# A-GSM.net
KiCad netlist of a schematic drawn in Altium Designer
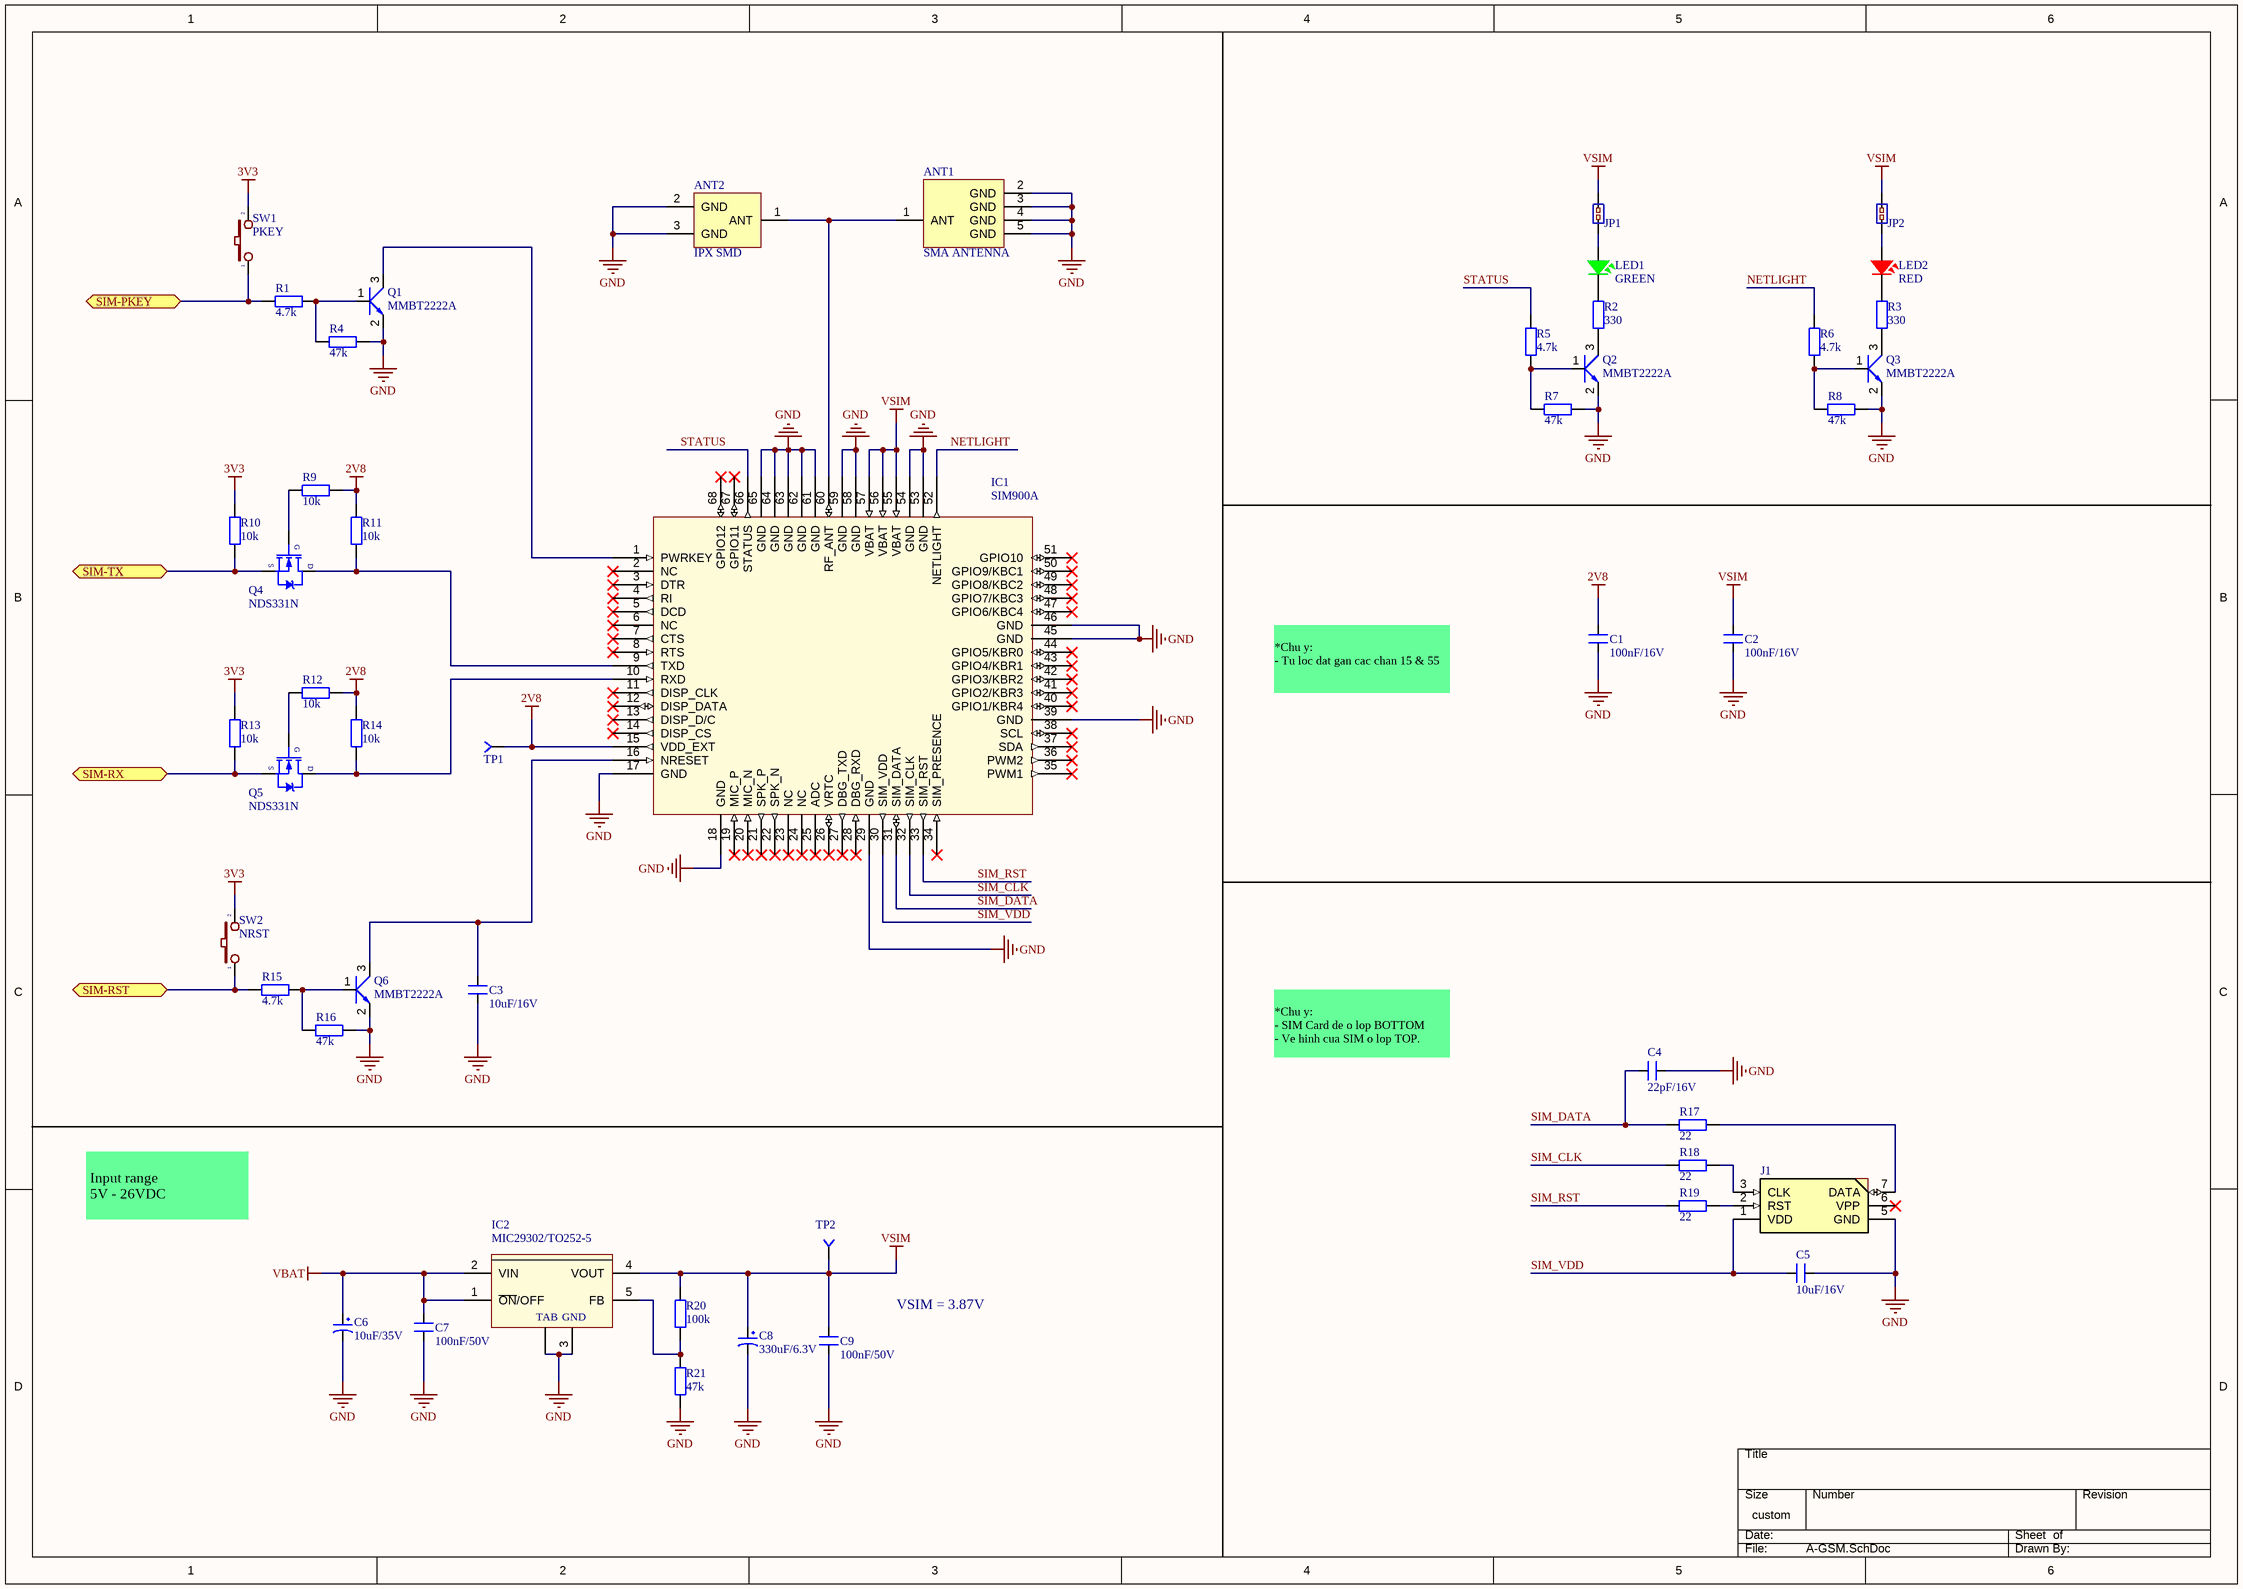
[diagram p0: A-GSM.SchDoc]

(export (version "E")
  (design (tool "Eeschema 10.0.6"))
  (components
    (comp (ref "ANT1")
      (value "SMA ANTENNA")
      (footprint "ANT-SMA-ST-F")
      (description "SMA Right-Angle PCB Female Antenna")
      (fields (field (name "Comment") "ANTEN-SMA"))
      (libsource (lib "Tran Tuan") (part "ANTEN-SMA"))
    )
    (comp (ref "ANT2")
      (value "IPX SMD")
      (footprint "ANT-IPX-SMD")
      (description "IPX, SMD, ANTENNA")
      (fields (field (name "Comment") "ANTEN-IPX"))
      (libsource (lib "Tran Tuan") (part "ANTEN-IPX"))
    )
    (comp (ref "C1")
      (value "100nF/16V")
      (footprint "C0805-2012")
      (description "CAP CER 0.1UF 16V X7R 0805")
      (fields
        (field (name "MANUFACTURER") "Kemet")
        (field (name "MANUFACTURER PART NUMBER") "C0805C104K4RACTU")
      )
      (libsource (lib "Tran Tuan") (part "CAP-CER/100nF/16V/X7R/0805"))
    )
    (comp (ref "C2")
      (value "100nF/16V")
      (footprint "C0805-2012")
      (description "CAP CER 0.1UF 16V X7R 0805")
      (fields
        (field (name "MANUFACTURER") "Kemet")
        (field (name "MANUFACTURER PART NUMBER") "C0805C104K4RACTU")
      )
      (libsource (lib "Tran Tuan") (part "CAP-CER/100nF/16V/X7R/0805"))
    )
    (comp (ref "C3")
      (value "10uF/16V")
      (footprint "C0805-2012")
      (description "CAP CER 10UF 16V X5R 0805")
      (fields
        (field (name "MANUFACTURER") "Murata Electronics North America")
        (field (name "MANUFACTURER PART NUMBER") "GRM21BR61C106KE15L")
      )
      (libsource (lib "Tran Tuan") (part "CAP-CER/10UF/16V/X5R/0805"))
    )
    (comp (ref "C4")
      (value "22pF/16V")
      (footprint "C0603-1608")
      (description "CAP CER 22PF 16V NP0 0603")
      (fields
        (field (name "MANUFACTURER") "Kemet")
        (field (name "MANUFACTURER PART NUMBER") "C0603C220K4GACTU")
      )
      (libsource (lib "Tran Tuan") (part "CAP-CER/22pF/16V/NP0/0603"))
    )
    (comp (ref "C5")
      (value "10uF/16V")
      (footprint "C0805-2012")
      (description "CAP CER 10UF 16V X5R 0805")
      (fields
        (field (name "MANUFACTURER") "Murata Electronics North America")
        (field (name "MANUFACTURER PART NUMBER") "GRM21BR61C106KE15L")
      )
      (libsource (lib "Tran Tuan") (part "CAP-CER/10UF/16V/X5R/0805"))
    )
    (comp (ref "C6")
      (value "10uF/35V")
      (footprint "CAP_TANTA_10UF_35V")
      (description "CAP TANT 10UF 35V 10% 2413")
      (fields
        (field (name "MANUFACTURER") "Kemet")
        (field (name "MANUFACTURER PART NUMBER") "T491C106K035AT")
      )
      (libsource (lib "Tran Tuan") (part "CAP-TANT/10uF/35V/2413"))
    )
    (comp (ref "C7")
      (value "100nF/50V")
      (footprint "C0805-2012")
      (description "CAP CER 0.1UF 50V X7R 0805")
      (fields
        (field (name "MANUFACTURER") "AVX Corporation")
        (field (name "MANUFACTURER PART NUMBER") "08055C104KAT2A")
      )
      (libsource (lib "Tran Tuan") (part "CAP-CER/100nF/50V/X7R/0805"))
    )
    (comp (ref "C8")
      (value "330uF/6.3V")
      (footprint "CAP_TANTA-3528")
      (description "CAP TAN 330UF 20% 6V 3528-21")
      (fields
        (field (name "MANUFACTURER") "Kemet")
        (field (name "MANUFACTURER PART NUMBER") "T490B337M006ATE800")
      )
      (libsource (lib "Tran Tuan") (part "CAP-TANT/330uF/6.3V/3528"))
    )
    (comp (ref "C9")
      (value "100nF/50V")
      (footprint "C0805-2012")
      (description "CAP CER 0.1UF 50V X7R 0805")
      (fields
        (field (name "MANUFACTURER") "AVX Corporation")
        (field (name "MANUFACTURER PART NUMBER") "08055C104KAT2A")
      )
      (libsource (lib "Tran Tuan") (part "CAP-CER/100nF/50V/X7R/0805"))
    )
    (comp (ref "IC1")
      (value "SIM900A/SIMCOM")
      (footprint "SIM900A")
      (description "SIM900A, Dual-band GSM/GPRS 900/1800MHz Module")
      (fields (field (name "MANUFACTURER") "SIMCOM") (field (name "MANUFACTURER PART NUMBER") "SIM900A"))
      (libsource (lib "Tran Tuan") (part "SIM900A/SIMCOM"))
    )
    (comp (ref "IC2")
      (value "MIC29302/TO252-5")
      (footprint "MIC29302A")
      (description "IC REG LDO ADJ 3A TO252-5")
      (fields
        (field (name "MANUFACTURER") "Microchip Technology")
        (field (name "MANUFACTURER PART NUMBER") "MIC29302AWD-TR")
      )
      (libsource (lib "Tran Tuan") (part "MIC29302/TO252-5"))
    )
    (comp (ref "J1")
      (value "SIM-FMS006-2620-0")
      (footprint "SIM-FMS006-2620-0")
      (description "SIM Card Conn 6-Pin Top, Mount, Push-Push")
      (libsource (lib "Tran Tuan") (part "SIM-FMS006-2620-0"))
    )
    (comp (ref "JP1")
      (value "JP2-ShortingJumper")
      (footprint "Header_2")
      (description "2.54mm 2-Pin Shorting Jumper")
      (libsource (lib "Tran Tuan") (part "JP2-ShortingJumper"))
    )
    (comp (ref "JP2")
      (value "JP2-ShortingJumper")
      (footprint "Header_2")
      (description "2.54mm 2-Pin Shorting Jumper")
      (libsource (lib "Tran Tuan") (part "JP2-ShortingJumper"))
    )
    (comp (ref "LED1")
      (value "GREEN")
      (footprint "Led 0805G")
      (description "LED GREEN CLEAR 0805 SMD")
      (fields
        (field (name "MANUFACTURER") "Lite-On Inc.")
        (field (name "MANUFACTURER PART NUMBER") "LTST-C171GKT")
      )
      (libsource (lib "Tran Tuan") (part "LED-GREEN/CLEAR/0805"))
    )
    (comp (ref "LED2")
      (value "RED")
      (footprint "Led 0805R")
      (description "LED RED CLEAR 0805 SMD")
      (fields
        (field (name "MANUFACTURER") "Lite-On Inc.")
        (field (name "MANUFACTURER PART NUMBER") "LTST-C171KRKT")
      )
      (libsource (lib "Tran Tuan") (part "LED-RED/CLEAR/0805"))
    )
    (comp (ref "Q1")
      (value "MMBT2222A")
      (footprint "MMBT2222A")
      (description "TRANS NPN 40V 0.6A SOT23")
      (fields
        (field (name "MANUFACTURER") "ON Semiconductor")
        (field (name "MANUFACTURER PART NUMBER") "MMBT2222ALT1G")
      )
      (libsource (lib "Tran Tuan") (part "BJT-MMBT2222A/SOT23"))
    )
    (comp (ref "Q2")
      (value "MMBT2222A")
      (footprint "MMBT2222A")
      (description "TRANS NPN 40V 0.6A SOT23")
      (fields
        (field (name "MANUFACTURER") "ON Semiconductor")
        (field (name "MANUFACTURER PART NUMBER") "MMBT2222ALT1G")
      )
      (libsource (lib "Tran Tuan") (part "BJT-MMBT2222A/SOT23"))
    )
    (comp (ref "Q3")
      (value "MMBT2222A")
      (footprint "MMBT2222A")
      (description "TRANS NPN 40V 0.6A SOT23")
      (fields
        (field (name "MANUFACTURER") "ON Semiconductor")
        (field (name "MANUFACTURER PART NUMBER") "MMBT2222ALT1G")
      )
      (libsource (lib "Tran Tuan") (part "BJT-MMBT2222A/SOT23"))
    )
    (comp (ref "Q4")
      (value "NDS331N")
      (footprint "NDS331N")
      (description "MOSFET N-CH 20V 1.3A SSOT3")
      (fields (field (name "MANUFACTURER") "Fairchild Semiconductor"))
      (libsource (lib "Tran Tuan") (part "MOSFET-NDS331N/SSOT3"))
    )
    (comp (ref "Q5")
      (value "NDS331N")
      (footprint "NDS331N")
      (description "MOSFET N-CH 20V 1.3A SSOT3")
      (fields (field (name "MANUFACTURER") "Fairchild Semiconductor"))
      (libsource (lib "Tran Tuan") (part "MOSFET-NDS331N/SSOT3"))
    )
    (comp (ref "Q6")
      (value "MMBT2222A")
      (footprint "MMBT2222A")
      (description "TRANS NPN 40V 0.6A SOT23")
      (fields
        (field (name "MANUFACTURER") "ON Semiconductor")
        (field (name "MANUFACTURER PART NUMBER") "MMBT2222ALT1G")
      )
      (libsource (lib "Tran Tuan") (part "BJT-MMBT2222A/SOT23"))
    )
    (comp (ref "R1")
      (value "~")
      (footprint "RESC2012(0805)")
      (description "RES SMD 4.7K OHM 5% 1/8W 0805")
      (fields
        (field (name "MANUFACTURER") "Yageo")
        (field (name "MANUFACTURER PART NUMBER") "RC0805JR-074K7L")
        (field (name "RESISTANCE (OHMS)") "4.7k")
      )
      (libsource (lib "") (part "RES-0805/±5%_2"))
    )
    (comp (ref "R2")
      (value "~")
      (footprint "RESC2012(0805)")
      (description "RES SMD 330 OHM 5% 1/8W 0805")
      (fields
        (field (name "MANUFACTURER") "Yageo")
        (field (name "MANUFACTURER PART NUMBER") "RC0805JR-07330RL")
        (field (name "RESISTANCE (OHMS)") "330")
      )
      (libsource (lib "Tran Tuan") (part "RES-0805/±5%"))
    )
    (comp (ref "R3")
      (value "~")
      (footprint "RESC2012(0805)")
      (description "RES SMD 330 OHM 5% 1/8W 0805")
      (fields
        (field (name "MANUFACTURER") "Yageo")
        (field (name "MANUFACTURER PART NUMBER") "RC0805JR-07330RL")
        (field (name "RESISTANCE (OHMS)") "330")
      )
      (libsource (lib "Tran Tuan") (part "RES-0805/±5%"))
    )
    (comp (ref "R4")
      (value "~")
      (footprint "RESC2012(0805)")
      (description "RES SMD 47K OHM 5% 1/8W 0805")
      (fields
        (field (name "MANUFACTURER") "Yageo")
        (field (name "MANUFACTURER PART NUMBER") "RC0805JR-0747KL")
        (field (name "RESISTANCE (OHMS)") "47k")
      )
      (libsource (lib "") (part "RES-0805/±5%_2"))
    )
    (comp (ref "R5")
      (value "~")
      (footprint "RESC2012(0805)")
      (description "RES SMD 4.7K OHM 5% 1/8W 0805")
      (fields
        (field (name "MANUFACTURER") "Yageo")
        (field (name "MANUFACTURER PART NUMBER") "RC0805JR-074K7L")
        (field (name "RESISTANCE (OHMS)") "4.7k")
      )
      (libsource (lib "Tran Tuan") (part "RES-0805/±5%"))
    )
    (comp (ref "R6")
      (value "~")
      (footprint "RESC2012(0805)")
      (description "RES SMD 4.7K OHM 5% 1/8W 0805")
      (fields
        (field (name "MANUFACTURER") "Yageo")
        (field (name "MANUFACTURER PART NUMBER") "RC0805JR-074K7L")
        (field (name "RESISTANCE (OHMS)") "4.7k")
      )
      (libsource (lib "Tran Tuan") (part "RES-0805/±5%"))
    )
    (comp (ref "R7")
      (value "~")
      (footprint "RESC2012(0805)")
      (description "RES SMD 47K OHM 5% 1/8W 0805")
      (fields
        (field (name "MANUFACTURER") "Yageo")
        (field (name "MANUFACTURER PART NUMBER") "RC0805JR-0747KL")
        (field (name "RESISTANCE (OHMS)") "47k")
      )
      (libsource (lib "") (part "RES-0805/±5%_2"))
    )
    (comp (ref "R8")
      (value "~")
      (footprint "RESC2012(0805)")
      (description "RES SMD 47K OHM 5% 1/8W 0805")
      (fields
        (field (name "MANUFACTURER") "Yageo")
        (field (name "MANUFACTURER PART NUMBER") "RC0805JR-0747KL")
        (field (name "RESISTANCE (OHMS)") "47k")
      )
      (libsource (lib "") (part "RES-0805/±5%_2"))
    )
    (comp (ref "R9")
      (value "~")
      (footprint "RESC2012(0805)")
      (description "RES SMD 10K OHM 5% 1/8W 0805")
      (fields
        (field (name "MANUFACTURER") "Yageo")
        (field (name "MANUFACTURER PART NUMBER") "RC0805JR-0710KL")
        (field (name "RESISTANCE (OHMS)") "10k")
      )
      (libsource (lib "") (part "RES-0805/±5%_2"))
    )
    (comp (ref "R10")
      (value "~")
      (footprint "RESC2012(0805)")
      (description "RES SMD 10K OHM 5% 1/8W 0805")
      (fields
        (field (name "MANUFACTURER") "Yageo")
        (field (name "MANUFACTURER PART NUMBER") "RC0805JR-0710KL")
        (field (name "RESISTANCE (OHMS)") "10k")
      )
      (libsource (lib "") (part "RES-0805/±5%_1"))
    )
    (comp (ref "R11")
      (value "~")
      (footprint "RESC2012(0805)")
      (description "RES SMD 10K OHM 5% 1/8W 0805")
      (fields
        (field (name "MANUFACTURER") "Yageo")
        (field (name "MANUFACTURER PART NUMBER") "RC0805JR-0710KL")
        (field (name "RESISTANCE (OHMS)") "10k")
      )
      (libsource (lib "") (part "RES-0805/±5%_1"))
    )
    (comp (ref "R12")
      (value "~")
      (footprint "RESC2012(0805)")
      (description "RES SMD 10K OHM 5% 1/8W 0805")
      (fields
        (field (name "MANUFACTURER") "Yageo")
        (field (name "MANUFACTURER PART NUMBER") "RC0805JR-0710KL")
        (field (name "RESISTANCE (OHMS)") "10k")
      )
      (libsource (lib "") (part "RES-0805/±5%_2"))
    )
    (comp (ref "R13")
      (value "~")
      (footprint "RESC2012(0805)")
      (description "RES SMD 10K OHM 5% 1/8W 0805")
      (fields
        (field (name "MANUFACTURER") "Yageo")
        (field (name "MANUFACTURER PART NUMBER") "RC0805JR-0710KL")
        (field (name "RESISTANCE (OHMS)") "10k")
      )
      (libsource (lib "") (part "RES-0805/±5%_1"))
    )
    (comp (ref "R14")
      (value "~")
      (footprint "RESC2012(0805)")
      (description "RES SMD 10K OHM 5% 1/8W 0805")
      (fields
        (field (name "MANUFACTURER") "Yageo")
        (field (name "MANUFACTURER PART NUMBER") "RC0805JR-0710KL")
        (field (name "RESISTANCE (OHMS)") "10k")
      )
      (libsource (lib "") (part "RES-0805/±5%_1"))
    )
    (comp (ref "R15")
      (value "~")
      (footprint "RESC2012(0805)")
      (description "RES SMD 4.7K OHM 5% 1/8W 0805")
      (fields
        (field (name "MANUFACTURER") "Yageo")
        (field (name "MANUFACTURER PART NUMBER") "RC0805JR-074K7L")
        (field (name "RESISTANCE (OHMS)") "4.7k")
      )
      (libsource (lib "") (part "RES-0805/±5%_2"))
    )
    (comp (ref "R16")
      (value "~")
      (footprint "RESC2012(0805)")
      (description "RES SMD 47K OHM 5% 1/8W 0805")
      (fields
        (field (name "MANUFACTURER") "Yageo")
        (field (name "MANUFACTURER PART NUMBER") "RC0805JR-0747KL")
        (field (name "RESISTANCE (OHMS)") "47k")
      )
      (libsource (lib "") (part "RES-0805/±5%_2"))
    )
    (comp (ref "R17")
      (value "~")
      (footprint "RESC2012(0805)")
      (description "RES SMD 22 OHM 5% 1/8W 0805")
      (fields
        (field (name "MANUFACTURER") "Yageo")
        (field (name "MANUFACTURER PART NUMBER") "RC0805JR-0722RL")
        (field (name "RESISTANCE (OHMS)") "22")
      )
      (libsource (lib "") (part "RES-0805/±5%_3"))
    )
    (comp (ref "R18")
      (value "~")
      (footprint "RESC2012(0805)")
      (description "RES SMD 22 OHM 5% 1/8W 0805")
      (fields
        (field (name "MANUFACTURER") "Yageo")
        (field (name "MANUFACTURER PART NUMBER") "RC0805JR-0722RL")
        (field (name "RESISTANCE (OHMS)") "22")
      )
      (libsource (lib "") (part "RES-0805/±5%_3"))
    )
    (comp (ref "R19")
      (value "~")
      (footprint "RESC2012(0805)")
      (description "RES SMD 22 OHM 5% 1/8W 0805")
      (fields
        (field (name "MANUFACTURER") "Yageo")
        (field (name "MANUFACTURER PART NUMBER") "RC0805JR-0722RL")
        (field (name "RESISTANCE (OHMS)") "22")
      )
      (libsource (lib "") (part "RES-0805/±5%_3"))
    )
    (comp (ref "R20")
      (value "~")
      (footprint "RESC2012(0805)")
      (description "RES SMD 100K OHM 5% 1/8W 0805")
      (fields
        (field (name "MANUFACTURER") "Yageo")
        (field (name "MANUFACTURER PART NUMBER") "RC0805JR-07100KL")
        (field (name "RESISTANCE (OHMS)") "100k")
      )
      (libsource (lib "") (part "RES-0805/±5%_1"))
    )
    (comp (ref "R21")
      (value "~")
      (footprint "RESC2012(0805)")
      (description "RES SMD 47K OHM 5% 1/8W 0805")
      (fields
        (field (name "MANUFACTURER") "Yageo")
        (field (name "MANUFACTURER PART NUMBER") "RC0805JR-0747KL")
        (field (name "RESISTANCE (OHMS)") "47k")
      )
      (libsource (lib "Tran Tuan") (part "RES-0805/±5%"))
    )
    (comp (ref "SW1")
      (value "PKEY")
      (footprint "BTN-EVQ-11A04M")
      (description "SWITCH TACTILE SPST-NO 0.02A 15V")
      (fields
        (field (name "MANUFACTURER") "Panasonic Electronic Components")
        (field (name "MANUFACTURER PART NUMBER") "EVQ-11A04M")
      )
      (libsource (lib "Tran Tuan") (part "SW2-PUSH/SPST/NO"))
    )
    (comp (ref "SW2")
      (value "NRST")
      (footprint "BTN-EVQ-11A04M")
      (description "SWITCH TACTILE SPST-NO 0.02A 15V")
      (fields
        (field (name "MANUFACTURER") "Panasonic Electronic Components")
        (field (name "MANUFACTURER PART NUMBER") "EVQ-11A04M")
      )
      (libsource (lib "Tran Tuan") (part "SW2-PUSH/SPST/NO"))
    )
    (comp (ref "TP1")
      (value "Test Point")
      (footprint "Test_point_VIA06")
      (description "Test Point, Pad, Hole")
      (libsource (lib "Tran Tuan") (part "Connector-TP"))
    )
    (comp (ref "TP2")
      (value "Test Point")
      (footprint "Test_point_VIA06")
      (description "Test Point, Pad, Hole")
      (libsource (lib "Tran Tuan") (part "Connector-TP"))
    )
  )
  (nets
    (net (code "1") (name "/NETLIGHT") (class "Default")
      (node (ref "IC1") (pin "52") (pinfunction "NETLIGHT_52") (pintype "output"))
      (node (ref "R6") (pin "2") (pinfunction "2_2") (pintype "passive"))
    )
    (net (code "2") (name "/SIM-PKEY") (class "Default")
      (node (ref "R1") (pin "1") (pinfunction "1_1") (pintype "passive"))
      (node (ref "SW1") (pin "1") (pinfunction "1_1") (pintype "passive"))
    )
    (net (code "3") (name "/SIM-RST") (class "Default")
      (node (ref "R15") (pin "1") (pinfunction "1_1") (pintype "passive"))
      (node (ref "SW2") (pin "1") (pinfunction "1_1") (pintype "passive"))
    )
    (net (code "4") (name "/SIM-RX") (class "Default")
      (node (ref "Q5") (pin "2") (pinfunction "S_2") (pintype "passive"))
      (node (ref "R13") (pin "2") (pinfunction "2_2") (pintype "passive"))
    )
    (net (code "5") (name "/SIM-TX") (class "Default")
      (node (ref "Q4") (pin "2") (pinfunction "S_2") (pintype "passive"))
      (node (ref "R10") (pin "2") (pinfunction "2_2") (pintype "passive"))
    )
    (net (code "6") (name "/SIM_CLK") (class "Default")
      (node (ref "IC1") (pin "32") (pinfunction "SIM_CLK_32") (pintype "output"))
      (node (ref "R18") (pin "2") (pinfunction "2_2") (pintype "passive"))
    )
    (net (code "7") (name "/SIM_DATA") (class "Default")
      (node (ref "C4") (pin "1") (pinfunction "1_1") (pintype "passive"))
      (node (ref "IC1") (pin "31") (pinfunction "SIM_DATA_31") (pintype "bidirectional"))
      (node (ref "R17") (pin "2") (pinfunction "2_2") (pintype "passive"))
    )
    (net (code "8") (name "/SIM_RST") (class "Default")
      (node (ref "IC1") (pin "33") (pinfunction "SIM_RST_33") (pintype "output"))
      (node (ref "R19") (pin "2") (pinfunction "2_2") (pintype "passive"))
    )
    (net (code "9") (name "/SIM_VDD") (class "Default")
      (node (ref "C5") (pin "1") (pinfunction "1_1") (pintype "passive"))
      (node (ref "IC1") (pin "30") (pinfunction "SIM_VDD_30") (pintype "output"))
      (node (ref "J1") (pin "1") (pinfunction "VDD_1") (pintype "passive"))
    )
    (net (code "10") (name "/STATUS") (class "Default")
      (node (ref "IC1") (pin "66") (pinfunction "STATUS_66") (pintype "output"))
      (node (ref "R5") (pin "2") (pinfunction "2_2") (pintype "passive"))
    )
    (net (code "11") (name "2V8") (class "Default")
      (node (ref "C1") (pin "1") (pinfunction "1_1") (pintype "passive"))
      (node (ref "IC1") (pin "15") (pinfunction "VDD_EXT_15") (pintype "output"))
      (node (ref "R11") (pin "1") (pinfunction "1_1") (pintype "passive"))
      (node (ref "R12") (pin "2") (pinfunction "2_2") (pintype "passive"))
      (node (ref "R14") (pin "1") (pinfunction "1_1") (pintype "passive"))
      (node (ref "R9") (pin "2") (pinfunction "2_2") (pintype "passive"))
      (node (ref "TP1") (pin "1") (pinfunction "1_1") (pintype "passive"))
    )
    (net (code "12") (name "3V3") (class "Default")
      (node (ref "R10") (pin "1") (pinfunction "1_1") (pintype "passive"))
      (node (ref "R13") (pin "1") (pinfunction "1_1") (pintype "passive"))
      (node (ref "SW1") (pin "2") (pinfunction "2_2") (pintype "passive"))
      (node (ref "SW2") (pin "2") (pinfunction "2_2") (pintype "passive"))
    )
    (net (code "13") (name "GND") (class "Default")
      (node (ref "ANT1") (pin "2") (pinfunction "GND_2") (pintype "power_in"))
      (node (ref "ANT1") (pin "3") (pinfunction "GND_3") (pintype "power_in"))
      (node (ref "ANT1") (pin "4") (pinfunction "GND_4") (pintype "power_in"))
      (node (ref "ANT1") (pin "5") (pinfunction "GND_5") (pintype "power_in"))
      (node (ref "ANT2") (pin "2") (pinfunction "GND_2") (pintype "power_in"))
      (node (ref "ANT2") (pin "3") (pinfunction "GND_3") (pintype "power_in"))
      (node (ref "C1") (pin "2") (pinfunction "2_2") (pintype "passive"))
      (node (ref "C2") (pin "2") (pinfunction "2_2") (pintype "passive"))
      (node (ref "C3") (pin "2") (pinfunction "2_2") (pintype "passive"))
      (node (ref "C4") (pin "2") (pinfunction "2_2") (pintype "passive"))
      (node (ref "C5") (pin "2") (pinfunction "2_2") (pintype "passive"))
      (node (ref "C6") (pin "2") (pinfunction "2_2") (pintype "passive"))
      (node (ref "C7") (pin "2") (pinfunction "2_2") (pintype "passive"))
      (node (ref "C8") (pin "2") (pinfunction "2_2") (pintype "passive"))
      (node (ref "C9") (pin "2") (pinfunction "2_2") (pintype "passive"))
      (node (ref "IC1") (pin "17") (pinfunction "GND_17") (pintype "power_in"))
      (node (ref "IC1") (pin "18") (pinfunction "GND_18") (pintype "power_in"))
      (node (ref "IC1") (pin "29") (pinfunction "GND_29") (pintype "power_in"))
      (node (ref "IC1") (pin "39") (pinfunction "GND_39") (pintype "power_in"))
      (node (ref "IC1") (pin "45") (pinfunction "GND_45") (pintype "power_in"))
      (node (ref "IC1") (pin "46") (pinfunction "GND_46") (pintype "power_in"))
      (node (ref "IC1") (pin "53") (pinfunction "GND_53") (pintype "power_in"))
      (node (ref "IC1") (pin "54") (pinfunction "GND_54") (pintype "power_in"))
      (node (ref "IC1") (pin "58") (pinfunction "GND_58") (pintype "power_in"))
      (node (ref "IC1") (pin "59") (pinfunction "GND_59") (pintype "power_in"))
      (node (ref "IC1") (pin "61") (pinfunction "GND_61") (pintype "power_in"))
      (node (ref "IC1") (pin "62") (pinfunction "GND_62") (pintype "power_in"))
      (node (ref "IC1") (pin "63") (pinfunction "GND_63") (pintype "power_in"))
      (node (ref "IC1") (pin "64") (pinfunction "GND_64") (pintype "power_in"))
      (node (ref "IC1") (pin "65") (pinfunction "GND_65") (pintype "power_in"))
      (node (ref "IC2") (pin "3") (pinfunction "GND_3") (pintype "power_in"))
      (node (ref "IC2") (pin "6") (pinfunction "TAB_6") (pintype "power_in"))
      (node (ref "J1") (pin "5") (pinfunction "GND_5") (pintype "passive"))
      (node (ref "Q1") (pin "2") (pinfunction "E_2") (pintype "passive"))
      (node (ref "Q2") (pin "2") (pinfunction "E_2") (pintype "passive"))
      (node (ref "Q3") (pin "2") (pinfunction "E_2") (pintype "passive"))
      (node (ref "Q6") (pin "2") (pinfunction "E_2") (pintype "passive"))
      (node (ref "R16") (pin "2") (pinfunction "2_2") (pintype "passive"))
      (node (ref "R21") (pin "1") (pinfunction "1_1") (pintype "passive"))
      (node (ref "R4") (pin "2") (pinfunction "2_2") (pintype "passive"))
      (node (ref "R7") (pin "2") (pinfunction "2_2") (pintype "passive"))
      (node (ref "R8") (pin "2") (pinfunction "2_2") (pintype "passive"))
    )
    (net (code "14") (name "Net-(ANT1-ANT)") (class "Default")
      (node (ref "ANT1") (pin "1") (pinfunction "ANT_1") (pintype "passive"))
      (node (ref "ANT2") (pin "1") (pinfunction "ANT_1") (pintype "passive"))
      (node (ref "IC1") (pin "60") (pinfunction "RF_ANT_60") (pintype "bidirectional"))
    )
    (net (code "15") (name "Net-(IC1-NRESET)") (class "Default")
      (node (ref "C3") (pin "1") (pinfunction "1_1") (pintype "passive"))
      (node (ref "IC1") (pin "16") (pinfunction "NRESET_16") (pintype "input"))
      (node (ref "Q6") (pin "3") (pinfunction "C_3") (pintype "passive"))
    )
    (net (code "16") (name "Net-(IC1-PWRKEY)") (class "Default")
      (node (ref "IC1") (pin "1") (pinfunction "PWRKEY_1") (pintype "input"))
      (node (ref "Q1") (pin "3") (pinfunction "C_3") (pintype "passive"))
    )
    (net (code "17") (name "Net-(IC1-RXD)") (class "Default")
      (node (ref "IC1") (pin "10") (pinfunction "RXD_10") (pintype "input"))
      (node (ref "Q5") (pin "3") (pinfunction "D_3") (pintype "passive"))
      (node (ref "R14") (pin "2") (pinfunction "2_2") (pintype "passive"))
    )
    (net (code "18") (name "Net-(IC1-TXD)") (class "Default")
      (node (ref "IC1") (pin "9") (pinfunction "TXD_9") (pintype "output"))
      (node (ref "Q4") (pin "3") (pinfunction "D_3") (pintype "passive"))
      (node (ref "R11") (pin "2") (pinfunction "2_2") (pintype "passive"))
    )
    (net (code "19") (name "Net-(IC2-FB)") (class "Default")
      (node (ref "IC2") (pin "5") (pinfunction "FB_5") (pintype "power_in"))
      (node (ref "R20") (pin "2") (pinfunction "2_2") (pintype "passive"))
      (node (ref "R21") (pin "2") (pinfunction "2_2") (pintype "passive"))
    )
    (net (code "20") (name "Net-(J1-CLK)") (class "Default")
      (node (ref "J1") (pin "3") (pinfunction "CLK_3") (pintype "input"))
      (node (ref "R18") (pin "1") (pinfunction "1_1") (pintype "passive"))
    )
    (net (code "21") (name "Net-(J1-DATA)") (class "Default")
      (node (ref "J1") (pin "7") (pinfunction "DATA_7") (pintype "bidirectional"))
      (node (ref "R17") (pin "1") (pinfunction "1_1") (pintype "passive"))
    )
    (net (code "22") (name "Net-(J1-RST)") (class "Default")
      (node (ref "J1") (pin "2") (pinfunction "RST_2") (pintype "input"))
      (node (ref "R19") (pin "1") (pinfunction "1_1") (pintype "passive"))
    )
    (net (code "23") (name "Net-(LED1-A)") (class "Default")
      (node (ref "JP1") (pin "1") (pinfunction "1_1") (pintype "passive"))
      (node (ref "LED1") (pin "1") (pinfunction "A_1") (pintype "passive"))
    )
    (net (code "24") (name "Net-(LED1-K)") (class "Default")
      (node (ref "LED1") (pin "2") (pinfunction "K_2") (pintype "passive"))
      (node (ref "R2") (pin "2") (pinfunction "2_2") (pintype "passive"))
    )
    (net (code "25") (name "Net-(LED2-A)") (class "Default")
      (node (ref "JP2") (pin "1") (pinfunction "1_1") (pintype "passive"))
      (node (ref "LED2") (pin "1") (pinfunction "A_1") (pintype "passive"))
    )
    (net (code "26") (name "Net-(LED2-K)") (class "Default")
      (node (ref "LED2") (pin "2") (pinfunction "K_2") (pintype "passive"))
      (node (ref "R3") (pin "2") (pinfunction "2_2") (pintype "passive"))
    )
    (net (code "27") (name "Net-(Q1-B)") (class "Default")
      (node (ref "Q1") (pin "1") (pinfunction "B_1") (pintype "passive"))
      (node (ref "R1") (pin "2") (pinfunction "2_2") (pintype "passive"))
      (node (ref "R4") (pin "1") (pinfunction "1_1") (pintype "passive"))
    )
    (net (code "28") (name "Net-(Q2-B)") (class "Default")
      (node (ref "Q2") (pin "1") (pinfunction "B_1") (pintype "passive"))
      (node (ref "R5") (pin "1") (pinfunction "1_1") (pintype "passive"))
      (node (ref "R7") (pin "1") (pinfunction "1_1") (pintype "passive"))
    )
    (net (code "29") (name "Net-(Q2-C)") (class "Default")
      (node (ref "Q2") (pin "3") (pinfunction "C_3") (pintype "passive"))
      (node (ref "R2") (pin "1") (pinfunction "1_1") (pintype "passive"))
    )
    (net (code "30") (name "Net-(Q3-B)") (class "Default")
      (node (ref "Q3") (pin "1") (pinfunction "B_1") (pintype "passive"))
      (node (ref "R6") (pin "1") (pinfunction "1_1") (pintype "passive"))
      (node (ref "R8") (pin "1") (pinfunction "1_1") (pintype "passive"))
    )
    (net (code "31") (name "Net-(Q3-C)") (class "Default")
      (node (ref "Q3") (pin "3") (pinfunction "C_3") (pintype "passive"))
      (node (ref "R3") (pin "1") (pinfunction "1_1") (pintype "passive"))
    )
    (net (code "32") (name "Net-(Q4-G)") (class "Default")
      (node (ref "Q4") (pin "1") (pinfunction "G_1") (pintype "passive"))
      (node (ref "R9") (pin "1") (pinfunction "1_1") (pintype "passive"))
    )
    (net (code "33") (name "Net-(Q5-G)") (class "Default")
      (node (ref "Q5") (pin "1") (pinfunction "G_1") (pintype "passive"))
      (node (ref "R12") (pin "1") (pinfunction "1_1") (pintype "passive"))
    )
    (net (code "34") (name "Net-(Q6-B)") (class "Default")
      (node (ref "Q6") (pin "1") (pinfunction "B_1") (pintype "passive"))
      (node (ref "R15") (pin "2") (pinfunction "2_2") (pintype "passive"))
      (node (ref "R16") (pin "1") (pinfunction "1_1") (pintype "passive"))
    )
    (net (code "35") (name "VBAT") (class "Default")
      (node (ref "C6") (pin "1") (pinfunction "1_1") (pintype "passive"))
      (node (ref "C7") (pin "1") (pinfunction "1_1") (pintype "passive"))
      (node (ref "IC2") (pin "1") (pinfunction "~{ON}/OFF_1") (pintype "power_in"))
      (node (ref "IC2") (pin "2") (pinfunction "VIN_2") (pintype "power_in"))
    )
    (net (code "36") (name "VSIM") (class "Default")
      (node (ref "C2") (pin "1") (pinfunction "1_1") (pintype "passive"))
      (node (ref "C8") (pin "1") (pinfunction "1_1") (pintype "passive"))
      (node (ref "C9") (pin "1") (pinfunction "1_1") (pintype "passive"))
      (node (ref "IC1") (pin "55") (pinfunction "VBAT_55") (pintype "input"))
      (node (ref "IC1") (pin "56") (pinfunction "VBAT_56") (pintype "input"))
      (node (ref "IC1") (pin "57") (pinfunction "VBAT_57") (pintype "input"))
      (node (ref "IC2") (pin "4") (pinfunction "VOUT_4") (pintype "power_in"))
      (node (ref "JP1") (pin "2") (pinfunction "2_2") (pintype "passive"))
      (node (ref "JP2") (pin "2") (pinfunction "2_2") (pintype "passive"))
      (node (ref "R20") (pin "1") (pinfunction "1_1") (pintype "passive"))
      (node (ref "TP2") (pin "1") (pinfunction "1_1") (pintype "passive"))
    )
    (net (code "37") (name "unconnected-(IC1-ADC-Pad25)") (class "Default")
      (node (ref "IC1") (pin "25") (pinfunction "ADC_25") (pintype "passive+no_connect"))
    )
    (net (code "38") (name "unconnected-(IC1-CTS-Pad7)") (class "Default")
      (node (ref "IC1") (pin "7") (pinfunction "CTS_7") (pintype "output+no_connect"))
    )
    (net (code "39") (name "unconnected-(IC1-DBG_RXD-Pad28)") (class "Default")
      (node (ref "IC1") (pin "28") (pinfunction "DBG_RXD_28") (pintype "input+no_connect"))
    )
    (net (code "40") (name "unconnected-(IC1-DBG_TXD-Pad27)") (class "Default")
      (node (ref "IC1") (pin "27") (pinfunction "DBG_TXD_27") (pintype "output+no_connect"))
    )
    (net (code "41") (name "unconnected-(IC1-DCD-Pad5)") (class "Default")
      (node (ref "IC1") (pin "5") (pinfunction "DCD_5") (pintype "output+no_connect"))
    )
    (net (code "42") (name "unconnected-(IC1-DISP_CLK-Pad11)") (class "Default")
      (node (ref "IC1") (pin "11") (pinfunction "DISP_CLK_11") (pintype "output+no_connect"))
    )
    (net (code "43") (name "unconnected-(IC1-DISP_CS-Pad14)") (class "Default")
      (node (ref "IC1") (pin "14") (pinfunction "DISP_CS_14") (pintype "output+no_connect"))
    )
    (net (code "44") (name "unconnected-(IC1-DISP_DATA-Pad12)") (class "Default")
      (node (ref "IC1") (pin "12") (pinfunction "DISP_DATA_12") (pintype "bidirectional+no_connect"))
    )
    (net (code "45") (name "unconnected-(IC1-DISP_D{slash}C-Pad13)") (class "Default")
      (node (ref "IC1") (pin "13") (pinfunction "DISP_D/C_13") (pintype "output+no_connect"))
    )
    (net (code "46") (name "unconnected-(IC1-DTR-Pad3)") (class "Default")
      (node (ref "IC1") (pin "3") (pinfunction "DTR_3") (pintype "input+no_connect"))
    )
    (net (code "47") (name "unconnected-(IC1-GPIO1{slash}KBR4-Pad40)") (class "Default")
      (node (ref "IC1") (pin "40") (pinfunction "GPIO1/KBR4_40") (pintype "bidirectional+no_connect"))
    )
    (net (code "48") (name "unconnected-(IC1-GPIO2{slash}KBR3-Pad41)") (class "Default")
      (node (ref "IC1") (pin "41") (pinfunction "GPIO2/KBR3_41") (pintype "bidirectional+no_connect"))
    )
    (net (code "49") (name "unconnected-(IC1-GPIO3{slash}KBR2-Pad42)") (class "Default")
      (node (ref "IC1") (pin "42") (pinfunction "GPIO3/KBR2_42") (pintype "bidirectional+no_connect"))
    )
    (net (code "50") (name "unconnected-(IC1-GPIO4{slash}KBR1-Pad43)") (class "Default")
      (node (ref "IC1") (pin "43") (pinfunction "GPIO4/KBR1_43") (pintype "bidirectional+no_connect"))
    )
    (net (code "51") (name "unconnected-(IC1-GPIO5{slash}KBR0-Pad44)") (class "Default")
      (node (ref "IC1") (pin "44") (pinfunction "GPIO5/KBR0_44") (pintype "bidirectional+no_connect"))
    )
    (net (code "52") (name "unconnected-(IC1-GPIO6{slash}KBC4-Pad47)") (class "Default")
      (node (ref "IC1") (pin "47") (pinfunction "GPIO6/KBC4_47") (pintype "bidirectional+no_connect"))
    )
    (net (code "53") (name "unconnected-(IC1-GPIO7{slash}KBC3-Pad48)") (class "Default")
      (node (ref "IC1") (pin "48") (pinfunction "GPIO7/KBC3_48") (pintype "bidirectional+no_connect"))
    )
    (net (code "54") (name "unconnected-(IC1-GPIO8{slash}KBC2-Pad49)") (class "Default")
      (node (ref "IC1") (pin "49") (pinfunction "GPIO8/KBC2_49") (pintype "bidirectional+no_connect"))
    )
    (net (code "55") (name "unconnected-(IC1-GPIO9{slash}KBC1-Pad50)") (class "Default")
      (node (ref "IC1") (pin "50") (pinfunction "GPIO9/KBC1_50") (pintype "bidirectional+no_connect"))
    )
    (net (code "56") (name "unconnected-(IC1-GPIO10-Pad51)") (class "Default")
      (node (ref "IC1") (pin "51") (pinfunction "GPIO10_51") (pintype "bidirectional+no_connect"))
    )
    (net (code "57") (name "unconnected-(IC1-GPIO11-Pad67)") (class "Default")
      (node (ref "IC1") (pin "67") (pinfunction "GPIO11_67") (pintype "bidirectional+no_connect"))
    )
    (net (code "58") (name "unconnected-(IC1-GPIO12-Pad68)") (class "Default")
      (node (ref "IC1") (pin "68") (pinfunction "GPIO12_68") (pintype "bidirectional+no_connect"))
    )
    (net (code "59") (name "unconnected-(IC1-MIC_N-Pad20)") (class "Default")
      (node (ref "IC1") (pin "20") (pinfunction "MIC_N_20") (pintype "input+no_connect"))
    )
    (net (code "60") (name "unconnected-(IC1-MIC_P-Pad19)") (class "Default")
      (node (ref "IC1") (pin "19") (pinfunction "MIC_P_19") (pintype "input+no_connect"))
    )
    (net (code "61") (name "unconnected-(IC1-NC-Pad2)") (class "Default")
      (node (ref "IC1") (pin "2") (pinfunction "NC_2") (pintype "tri_state+no_connect"))
    )
    (net (code "62") (name "unconnected-(IC1-NC-Pad6)") (class "Default")
      (node (ref "IC1") (pin "6") (pinfunction "NC_6") (pintype "tri_state+no_connect"))
    )
    (net (code "63") (name "unconnected-(IC1-NC-Pad23)") (class "Default")
      (node (ref "IC1") (pin "23") (pinfunction "NC_23") (pintype "tri_state+no_connect"))
    )
    (net (code "64") (name "unconnected-(IC1-NC-Pad24)") (class "Default")
      (node (ref "IC1") (pin "24") (pinfunction "NC_24") (pintype "tri_state+no_connect"))
    )
    (net (code "65") (name "unconnected-(IC1-PWM1-Pad35)") (class "Default")
      (node (ref "IC1") (pin "35") (pinfunction "PWM1_35") (pintype "output+no_connect"))
    )
    (net (code "66") (name "unconnected-(IC1-PWM2-Pad36)") (class "Default")
      (node (ref "IC1") (pin "36") (pinfunction "PWM2_36") (pintype "output+no_connect"))
    )
    (net (code "67") (name "unconnected-(IC1-RI-Pad4)") (class "Default")
      (node (ref "IC1") (pin "4") (pinfunction "RI_4") (pintype "output+no_connect"))
    )
    (net (code "68") (name "unconnected-(IC1-RTS-Pad8)") (class "Default")
      (node (ref "IC1") (pin "8") (pinfunction "RTS_8") (pintype "input+no_connect"))
    )
    (net (code "69") (name "unconnected-(IC1-SCL-Pad38)") (class "Default")
      (node (ref "IC1") (pin "38") (pinfunction "SCL_38") (pintype "bidirectional+no_connect"))
    )
    (net (code "70") (name "unconnected-(IC1-SDA-Pad37)") (class "Default")
      (node (ref "IC1") (pin "37") (pinfunction "SDA_37") (pintype "output+no_connect"))
    )
    (net (code "71") (name "unconnected-(IC1-SIM_PRESENCE-Pad34)") (class "Default")
      (node (ref "IC1") (pin "34") (pinfunction "SIM_PRESENCE_34") (pintype "input+no_connect"))
    )
    (net (code "72") (name "unconnected-(IC1-SPK_N-Pad22)") (class "Default")
      (node (ref "IC1") (pin "22") (pinfunction "SPK_N_22") (pintype "output+no_connect"))
    )
    (net (code "73") (name "unconnected-(IC1-SPK_P-Pad21)") (class "Default")
      (node (ref "IC1") (pin "21") (pinfunction "SPK_P_21") (pintype "output+no_connect"))
    )
    (net (code "74") (name "unconnected-(IC1-VRTC-Pad26)") (class "Default")
      (node (ref "IC1") (pin "26") (pinfunction "VRTC_26") (pintype "bidirectional+no_connect"))
    )
    (net (code "75") (name "unconnected-(J1-VPP-Pad6)") (class "Default")
      (node (ref "J1") (pin "6") (pinfunction "VPP_6") (pintype "passive+no_connect"))
    )
  )
)
